# n24cape_rev_a.net
KiCad netlist of a schematic drawn in EAGLE
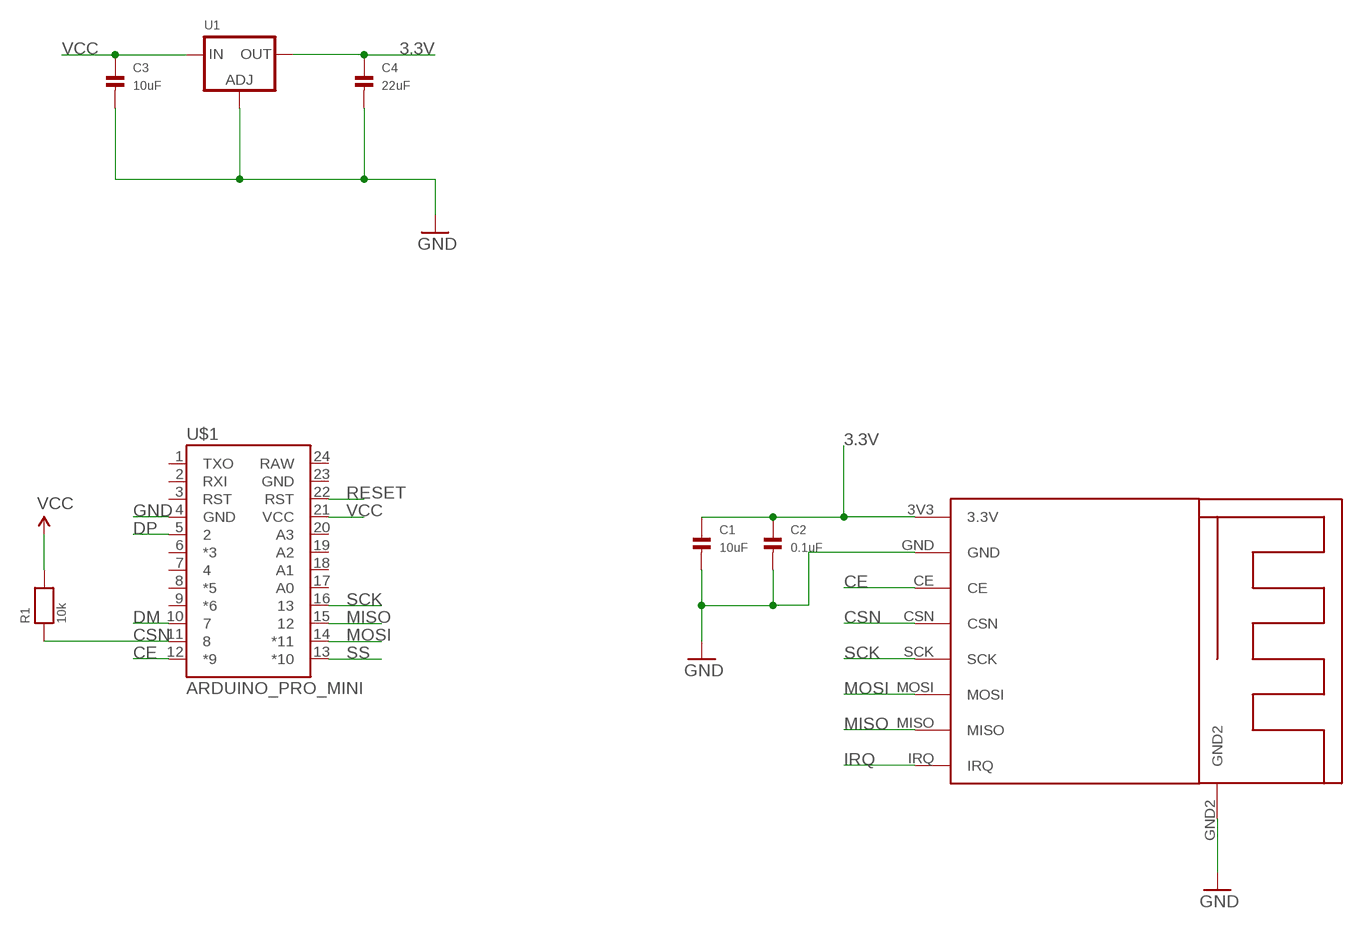
[diagram p0: schematic, sheet 1]

(export (version "E")
  (design (tool "Eeschema 10.0.6"))
  (components
    (comp (ref "C1")
      (value "10uF")
      (footprint "eagle-import:0603-MINI")
      (libsource (lib "eagle-import") (part "CAP_CERAMIC0603MINI"))
    )
    (comp (ref "C2")
      (value "0.1uF")
      (footprint "eagle-import:0603-MINI")
      (libsource (lib "eagle-import") (part "CAP_CERAMIC0603MINI"))
    )
    (comp (ref "C3")
      (value "10uF")
      (footprint "eagle-import:0603-MINI")
      (libsource (lib "eagle-import") (part "CAP_CERAMIC0603MINI"))
    )
    (comp (ref "C4")
      (value "22uF")
      (footprint "eagle-import:0603-MINI")
      (libsource (lib "eagle-import") (part "CAP_CERAMIC0603MINI"))
    )
    (comp (ref "R1")
      (value "10k")
      (footprint "eagle-import:_0603")
      (libsource (lib "eagle-import") (part "RESISTOR_0603"))
    )
    (comp (ref "U$1")
      (value "ARDUINO_PRO_MINI")
      (footprint "eagle-import:ARDUINO_PRO_MINI")
      (libsource (lib "eagle-import") (part "ARDUINO_PRO_MINI"))
    )
    (comp (ref "U$3")
      (value "NRF24MINI")
      (footprint "eagle-import:NRF24MINI")
      (libsource (lib "eagle-import") (part "NRF24MINI"))
    )
    (comp (ref "U1")
      (value "LM1117SOT223-REFLOW")
      (footprint "eagle-import:SOT223-R")
      (libsource (lib "eagle-import") (part "LM1117SOT223-REFLOW"))
    )
  )
  (nets
    (net (code "1") (name "/3.3V") (class "Default")
      (node (ref "C1") (pin "1") (pinfunction "P$1_1") (pintype "passive"))
      (node (ref "C2") (pin "1") (pinfunction "P$1_1") (pintype "passive"))
      (node (ref "C4") (pin "1") (pinfunction "P$1_1") (pintype "passive"))
      (node (ref "U$3") (pin "3V3") (pinfunction "3.3V_3V3") (pintype "bidirectional"))
      (node (ref "U1") (pin "2") (pinfunction "OUT_2") (pintype "passive"))
      (node (ref "U1") (pin "4") (pinfunction "OUT_4") (pintype "passive"))
    )
    (net (code "2") (name "/CE") (class "Default")
      (node (ref "U$1") (pin "12") (pinfunction "*9_12") (pintype "bidirectional"))
      (node (ref "U$3") (pin "CE") (pinfunction "CE_CE") (pintype "bidirectional"))
    )
    (net (code "3") (name "/CSN") (class "Default")
      (node (ref "R1") (pin "1") (pinfunction "1_1") (pintype "passive"))
      (node (ref "U$1") (pin "11") (pinfunction "8_11") (pintype "bidirectional"))
      (node (ref "U$3") (pin "CSN") (pinfunction "CSN_CSN") (pintype "bidirectional"))
    )
    (net (code "4") (name "/DM") (class "Default")
      (node (ref "U$1") (pin "10") (pinfunction "7_10") (pintype "bidirectional"))
    )
    (net (code "5") (name "/DP") (class "Default")
      (node (ref "U$1") (pin "5") (pinfunction "2_5") (pintype "bidirectional"))
    )
    (net (code "6") (name "/IRQ") (class "Default")
      (node (ref "U$3") (pin "IRQ") (pinfunction "IRQ_IRQ") (pintype "bidirectional"))
    )
    (net (code "7") (name "/MISO") (class "Default")
      (node (ref "U$1") (pin "15") (pinfunction "12_15") (pintype "bidirectional"))
      (node (ref "U$3") (pin "MISO") (pinfunction "MISO_MISO") (pintype "bidirectional"))
    )
    (net (code "8") (name "/MOSI") (class "Default")
      (node (ref "U$1") (pin "14") (pinfunction "*11_14") (pintype "bidirectional"))
      (node (ref "U$3") (pin "MOSI") (pinfunction "MOSI_MOSI") (pintype "bidirectional"))
    )
    (net (code "9") (name "/RESET") (class "Default")
      (node (ref "U$1") (pin "22") (pinfunction "RST_22") (pintype "bidirectional"))
    )
    (net (code "10") (name "/SCK") (class "Default")
      (node (ref "U$1") (pin "16") (pinfunction "13_16") (pintype "bidirectional"))
      (node (ref "U$3") (pin "SCK") (pinfunction "SCK_SCK") (pintype "bidirectional"))
    )
    (net (code "11") (name "/SS") (class "Default")
      (node (ref "U$1") (pin "13") (pinfunction "*10_13") (pintype "bidirectional"))
    )
    (net (code "12") (name "GND") (class "Default")
      (node (ref "C1") (pin "2") (pinfunction "P$2_2") (pintype "passive"))
      (node (ref "C2") (pin "2") (pinfunction "P$2_2") (pintype "passive"))
      (node (ref "C3") (pin "2") (pinfunction "P$2_2") (pintype "passive"))
      (node (ref "C4") (pin "2") (pinfunction "P$2_2") (pintype "passive"))
      (node (ref "U$1") (pin "4") (pinfunction "GND_4") (pintype "bidirectional"))
      (node (ref "U$3") (pin "GND") (pinfunction "GND_GND") (pintype "bidirectional"))
      (node (ref "U$3") (pin "GND2") (pinfunction "GND2_GND2") (pintype "bidirectional"))
      (node (ref "U1") (pin "1") (pinfunction "ADJ_1") (pintype "input"))
    )
    (net (code "13") (name "VCC") (class "Default")
      (node (ref "C3") (pin "1") (pinfunction "P$1_1") (pintype "passive"))
      (node (ref "R1") (pin "2") (pinfunction "2_2") (pintype "passive"))
      (node (ref "U$1") (pin "21") (pinfunction "VCC_21") (pintype "bidirectional"))
      (node (ref "U1") (pin "3") (pinfunction "IN_3") (pintype "input"))
    )
    (net (code "14") (name "unconnected-(U$1-*3-Pad6)") (class "Default")
      (node (ref "U$1") (pin "6") (pinfunction "*3_6") (pintype "bidirectional"))
    )
    (net (code "15") (name "unconnected-(U$1-*5-Pad8)") (class "Default")
      (node (ref "U$1") (pin "8") (pinfunction "*5_8") (pintype "bidirectional"))
    )
    (net (code "16") (name "unconnected-(U$1-*6-Pad9)") (class "Default")
      (node (ref "U$1") (pin "9") (pinfunction "*6_9") (pintype "bidirectional"))
    )
    (net (code "17") (name "unconnected-(U$1-4-Pad7)") (class "Default")
      (node (ref "U$1") (pin "7") (pinfunction "4_7") (pintype "bidirectional"))
    )
    (net (code "18") (name "unconnected-(U$1-A0-Pad17)") (class "Default")
      (node (ref "U$1") (pin "17") (pinfunction "A0_17") (pintype "bidirectional"))
    )
    (net (code "19") (name "unconnected-(U$1-A1-Pad18)") (class "Default")
      (node (ref "U$1") (pin "18") (pinfunction "A1_18") (pintype "bidirectional"))
    )
    (net (code "20") (name "unconnected-(U$1-A2-Pad19)") (class "Default")
      (node (ref "U$1") (pin "19") (pinfunction "A2_19") (pintype "bidirectional"))
    )
    (net (code "21") (name "unconnected-(U$1-A3-Pad20)") (class "Default")
      (node (ref "U$1") (pin "20") (pinfunction "A3_20") (pintype "bidirectional"))
    )
    (net (code "22") (name "unconnected-(U$1-GND-Pad23)") (class "Default")
      (node (ref "U$1") (pin "23") (pinfunction "GND_23") (pintype "bidirectional"))
    )
    (net (code "23") (name "unconnected-(U$1-RAW-Pad24)") (class "Default")
      (node (ref "U$1") (pin "24") (pinfunction "RAW_24") (pintype "bidirectional"))
    )
    (net (code "24") (name "unconnected-(U$1-RST-Pad3)") (class "Default")
      (node (ref "U$1") (pin "3") (pinfunction "RST_3") (pintype "bidirectional"))
    )
    (net (code "25") (name "unconnected-(U$1-RXI-Pad2)") (class "Default")
      (node (ref "U$1") (pin "2") (pinfunction "RXI_2") (pintype "bidirectional"))
    )
    (net (code "26") (name "unconnected-(U$1-TXO-Pad1)") (class "Default")
      (node (ref "U$1") (pin "1") (pinfunction "TXO_1") (pintype "bidirectional"))
    )
  )
)
